# TIDA-00042_SCHEMAT_C.net
KiCad netlist of a schematic drawn in Altium Designer
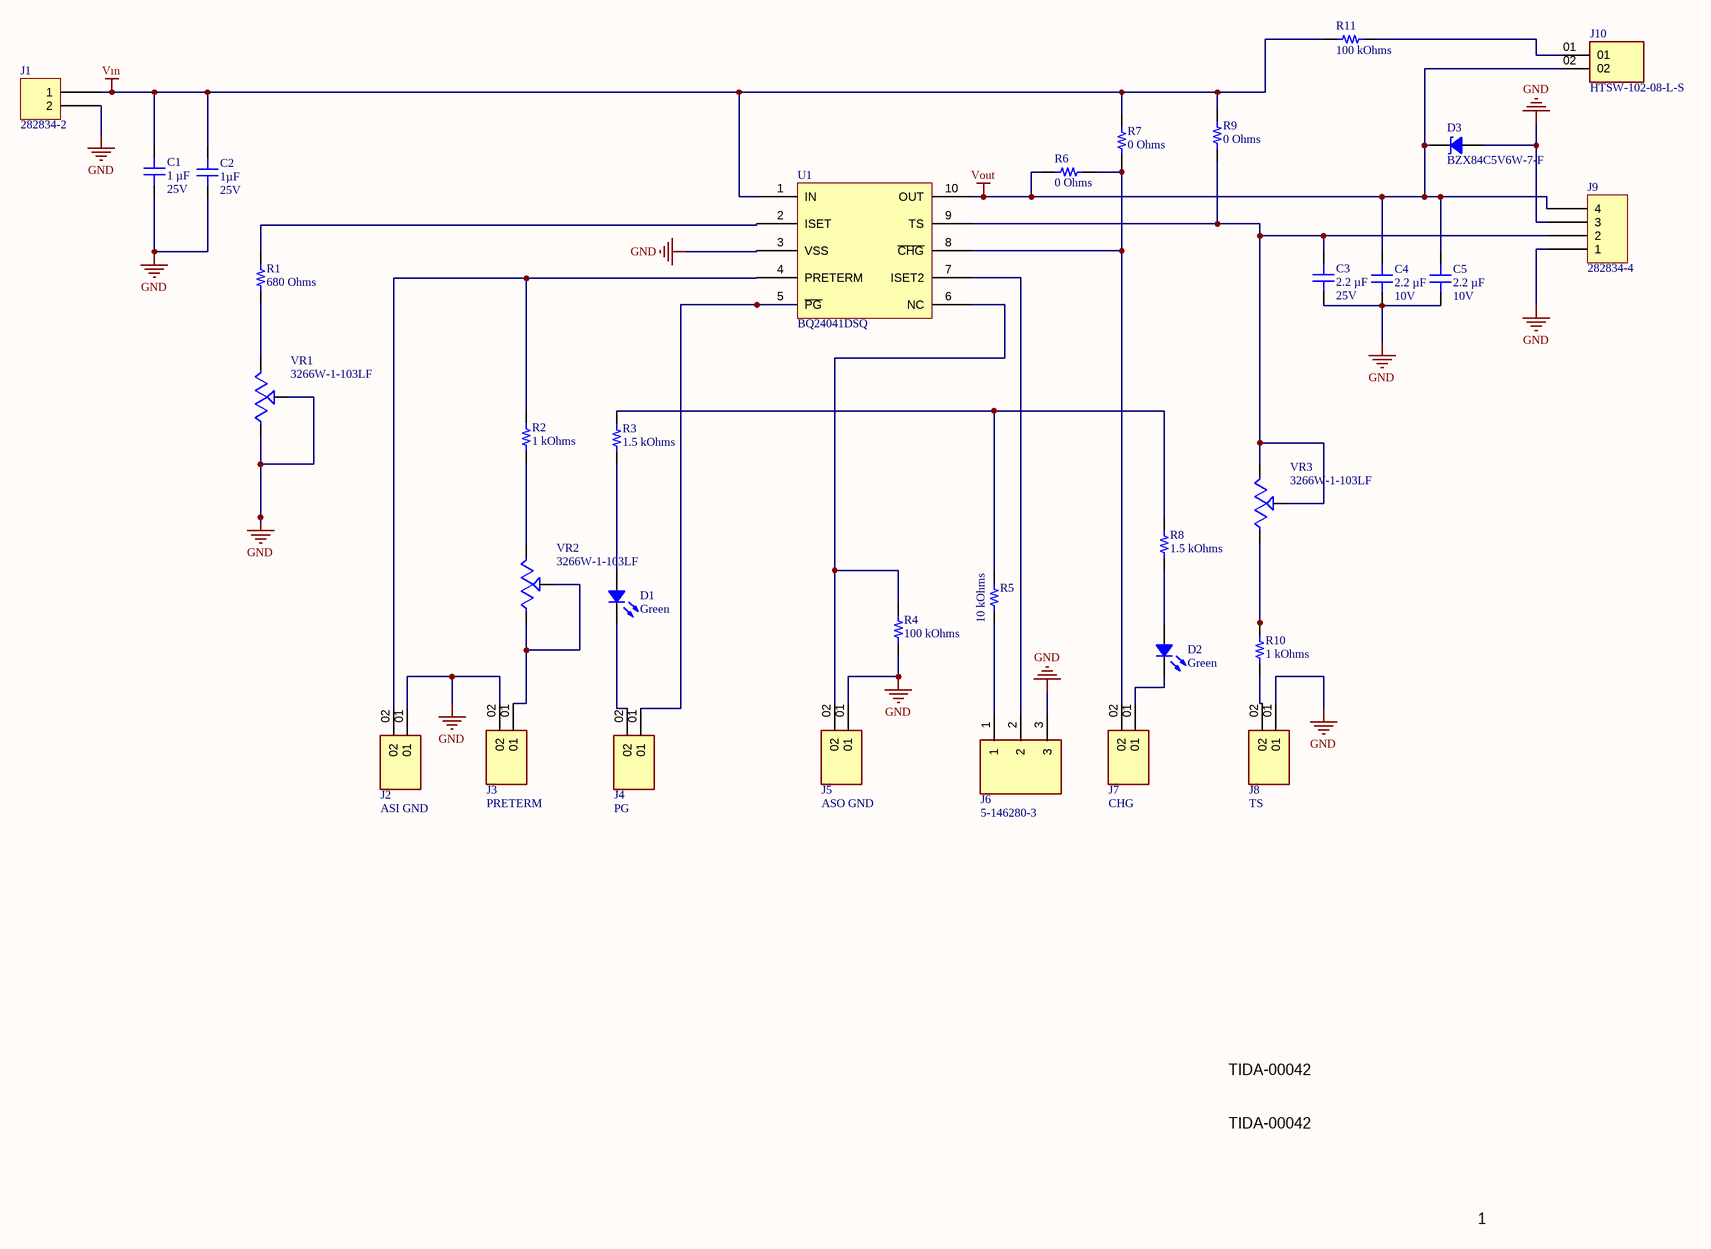
[diagram p0: TIDA-00042 SCHEMATİC.SchDoc]

(export (version "E")
  (design (tool "Eeschema 10.0.6"))
  (components
    (comp (ref "C1")
      (value "1 µF")
      (footprint "CAP 0603_1608")
      (description "CAP CER 1UF 25V X5R 0603")
      (fields
        (field (name "PART NUMBER") "CC0603KRX5R8BB105")
        (field (name "MANUFACTURER") "Yageo")
        (field (name "VOLTAGE - RATED") "25V")
      )
      (libsource (lib "Celestial Altium Library - altium_library") (part "Capacitor"))
    )
    (comp (ref "C2")
      (value "1µF")
      (footprint "CAP 0805_2012")
      (description "CAP CER 1UF 25V X5R 0805")
      (fields
        (field (name "PART NUMBER") "08053D105KAT2A")
        (field (name "MANUFACTURER") "AVX Corporation")
        (field (name "VOLTAGE - RATED") "25V")
      )
      (libsource (lib "Celestial Altium Library - altium_library") (part "Capacitor"))
    )
    (comp (ref "C3")
      (value "2.2 µF")
      (footprint "CAP 0603_1608")
      (description "CAP CER 2.2UF 25V X5R 0603")
      (fields
        (field (name "PART NUMBER") "CL10A225KA5LNNC")
        (field (name "MANUFACTURER") "Samsung Electro-Mechanics")
        (field (name "VOLTAGE - RATED") "25V")
      )
      (libsource (lib "Celestial Altium Library - altium_library") (part "Capacitor"))
    )
    (comp (ref "C4")
      (value "2.2 µF")
      (footprint "CAP 0603_1608")
      (description "CAP CER 2.2UF 10V X5R 0603")
      (fields
        (field (name "PART NUMBER") "CL10A225KP8NNNC")
        (field (name "MANUFACTURER") "Samsung Electro-Mechanics")
        (field (name "VOLTAGE - RATED") "10V")
      )
      (libsource (lib "Celestial Altium Library - altium_library") (part "Capacitor"))
    )
    (comp (ref "C5")
      (value "2.2 µF")
      (footprint "CAP 0805_2012")
      (description "CAP CER 2.2UF 10V X5R 0805")
      (fields
        (field (name "PART NUMBER") "CC0805KKX5R6BB225")
        (field (name "MANUFACTURER") "Yageo")
        (field (name "VOLTAGE - RATED") "10V")
      )
      (libsource (lib "Celestial Altium Library - altium_library") (part "Capacitor"))
    )
    (comp (ref "D1")
      (value "Green")
      (footprint "LED 0603_1608 GREEN")
      (description "LED GREEN CLEAR CHIP SMD")
      (fields (field (name "PART NUMBER") "LTST-C190GKT") (field (name "MANUFACTURER") "Lite-On Inc."))
      (libsource (lib "Celestial Altium Library - altium_library") (part "LED"))
    )
    (comp (ref "D2")
      (value "Green")
      (footprint "LED 0603_1608 GREEN")
      (description "LED GREEN CLEAR CHIP SMD")
      (fields (field (name "PART NUMBER") "LTST-C190GKT") (field (name "MANUFACTURER") "Lite-On Inc."))
      (libsource (lib "Celestial Altium Library - altium_library") (part "LED"))
    )
    (comp (ref "D3")
      (value "BZX84C5V6W-7-F")
      (footprint "DIODES SOT-323-3")
      (description "DIODE ZENER 5.6V 200MW SOT323")
      (fields (field (name "MANUFACTURER") "Diodes Incorporated") (field (name "TOLERANCE") "±7%"))
      (libsource (lib "Celestial Altium Library - altium_library") (part "Diode Zener"))
    )
    (comp (ref "J1")
      (value "282834-2")
      (footprint "TE 282834-2")
      (description "TERM BLK 2P SIDE ENT 2.54MM PCB")
      (fields (field (name "MANUFACTURER") "TE Connectivity AMP Connectors") (field (name "VOLTAGE") "150V"))
      (libsource (lib "Celestial Altium Library - altium_library") (part "2 Pin"))
    )
    (comp (ref "J2")
      (value "ASI GND")
      (footprint "SAMTEC_HTSW-102-08-L-S:SAMTEC_HTSW-102-08-L-S")
      (description "Conn Unshrouded Header HDR 2 POS 2.54mm Solder ST Top Entry Thru-Hole Bag")
      (fields (field (name "MP") "HTSW-102-08-L-S") (field (name "MF") "Samtec Inc."))
      (libsource (lib "HTSW-102-08-L-S") (part "HTSW-102-08-L-S"))
    )
    (comp (ref "J3")
      (value "PRETERM")
      (footprint "SAMTEC_HTSW-102-08-L-S:SAMTEC_HTSW-102-08-L-S")
      (description "Conn Unshrouded Header HDR 2 POS 2.54mm Solder ST Top Entry Thru-Hole Bag")
      (fields (field (name "MP") "HTSW-102-08-L-S") (field (name "MF") "Samtec Inc."))
      (libsource (lib "HTSW-102-08-L-S") (part "HTSW-102-08-L-S"))
    )
    (comp (ref "J4")
      (value "PG")
      (footprint "SAMTEC_HTSW-102-08-L-S:SAMTEC_HTSW-102-08-L-S")
      (description "Conn Unshrouded Header HDR 2 POS 2.54mm Solder ST Top Entry Thru-Hole Bag")
      (fields (field (name "MP") "HTSW-102-08-L-S") (field (name "MF") "Samtec Inc."))
      (libsource (lib "HTSW-102-08-L-S") (part "HTSW-102-08-L-S"))
    )
    (comp (ref "J5")
      (value "ASO GND")
      (footprint "SAMTEC_HTSW-102-08-L-S:SAMTEC_HTSW-102-08-L-S")
      (description "Conn Unshrouded Header HDR 2 POS 2.54mm Solder ST Top Entry Thru-Hole Bag")
      (fields (field (name "MP") "HTSW-102-08-L-S") (field (name "MF") "Samtec Inc."))
      (libsource (lib "HTSW-102-08-L-S") (part "HTSW-102-08-L-S"))
    )
    (comp (ref "J6")
      (value "5-146280-3")
      (footprint "SnapEDApcb:TE_5-146280-3")
      (description "Header; Conn; Interconnect System; PCB Plug; 3 Cont; Thru-Hole; Breakaway; Straight; 3A")
      (fields (field (name "MF") "TE Connectivity"))
      (libsource (lib "SnapEDAsch") (part "5-146280-3"))
    )
    (comp (ref "J7")
      (value "CHG")
      (footprint "SAMTEC_HTSW-102-08-L-S:SAMTEC_HTSW-102-08-L-S")
      (description "Conn Unshrouded Header HDR 2 POS 2.54mm Solder ST Top Entry Thru-Hole Bag")
      (fields (field (name "MP") "HTSW-102-08-L-S") (field (name "MF") "Samtec Inc."))
      (libsource (lib "HTSW-102-08-L-S") (part "HTSW-102-08-L-S"))
    )
    (comp (ref "J8")
      (value "TS")
      (footprint "SAMTEC_HTSW-102-08-L-S:SAMTEC_HTSW-102-08-L-S")
      (description "Conn Unshrouded Header HDR 2 POS 2.54mm Solder ST Top Entry Thru-Hole Bag")
      (fields (field (name "MP") "HTSW-102-08-L-S") (field (name "MF") "Samtec Inc."))
      (libsource (lib "HTSW-102-08-L-S") (part "HTSW-102-08-L-S"))
    )
    (comp (ref "J9")
      (value "282834-4")
      (footprint "TE 282834-4")
      (description "TERM BLK 4P SIDE ENT 2.54MM PCB")
      (fields (field (name "MANUFACTURER") "TE Connectivity AMP Connectors") (field (name "VOLTAGE") "150V"))
      (libsource (lib "Celestial Altium Library - altium_library") (part "4 Pin"))
    )
    (comp (ref "J10")
      (value "HTSW-102-08-L-S")
      (footprint "SAMTEC_HTSW-102-08-L-S:SAMTEC_HTSW-102-08-L-S")
      (description "Conn Unshrouded Header HDR 2 POS 2.54mm Solder ST Top Entry Thru-Hole Bag")
      (fields (field (name "MF") "Samtec Inc."))
      (libsource (lib "") (part "HTSW-102-08-L-S_1"))
    )
    (comp (ref "R1")
      (value "680 Ohms")
      (footprint "RES 0603_1608")
      (description "RES SMD 680 OHM 1% 1/10W 0603")
      (fields (field (name "PART NUMBER") "CRCW0603680RFKEA") (field (name "MANUFACTURER") "Vishay Dale"))
      (libsource (lib "Celestial Altium Library - altium_library") (part "Resistor"))
    )
    (comp (ref "R2")
      (value "1 kOhms")
      (footprint "RES 0603_1608")
      (description "RES SMD 1K OHM 1% 1/16W 0603")
      (fields
        (field (name "PART NUMBER") "CPF0603F1K0C1")
        (field (name "MANUFACTURER") "TE Connectivity Passive Product")
      )
      (libsource (lib "Celestial Altium Library - altium_library") (part "Resistor"))
    )
    (comp (ref "R3")
      (value "1.5 kOhms")
      (footprint "RES 0603_1608")
      (description "RES SMD 1.5K OHM 1% 1/10W 0603")
      (fields (field (name "PART NUMBER") "CRCW06031K50FKEA") (field (name "MANUFACTURER") "Vishay Dale"))
      (libsource (lib "Celestial Altium Library - altium_library") (part "Resistor"))
    )
    (comp (ref "R4")
      (value "100 kOhms")
      (footprint "RES 0603_1608")
      (description "RES 100K OHM 1% 1/10W 0603")
      (fields (field (name "PART NUMBER") "CRCW0603100KFKEBC") (field (name "MANUFACTURER") "Vishay Dale"))
      (libsource (lib "Celestial Altium Library - altium_library") (part "Resistor"))
    )
    (comp (ref "R5")
      (value "10 kOhms")
      (footprint "RES 0603_1608")
      (description "RES SMD 10K OHM 1% 1/16W 0603")
      (fields
        (field (name "PART NUMBER") "CPF0603F10KC1")
        (field (name "MANUFACTURER") "TE Connectivity Passive Product")
      )
      (libsource (lib "Celestial Altium Library - altium_library") (part "Resistor"))
    )
    (comp (ref "R6")
      (value "0 Ohms")
      (footprint "RES 0603_1608")
      (description "RES SMD 0 OHM JUMPER 1/10W 0603")
      (fields
        (field (name "PART NUMBER") "CRG0603ZR")
        (field (name "MANUFACTURER") "TE Connectivity Passive Product")
      )
      (libsource (lib "Celestial Altium Library - altium_library") (part "Resistor"))
    )
    (comp (ref "R7")
      (value "0 Ohms")
      (footprint "RES 0603_1608")
      (description "RES SMD 0 OHM JUMPER 1/10W 0603")
      (fields
        (field (name "PART NUMBER") "CRG0603ZR")
        (field (name "MANUFACTURER") "TE Connectivity Passive Product")
      )
      (libsource (lib "Celestial Altium Library - altium_library") (part "Resistor"))
    )
    (comp (ref "R8")
      (value "1.5 kOhms")
      (footprint "RES 0603_1608")
      (description "RES SMD 1.5K OHM 1% 1/10W 0603")
      (fields (field (name "PART NUMBER") "CRCW06031K50FKEA") (field (name "MANUFACTURER") "Vishay Dale"))
      (libsource (lib "Celestial Altium Library - altium_library") (part "Resistor"))
    )
    (comp (ref "R9")
      (value "0 Ohms")
      (footprint "RES 0603_1608")
      (description "RES SMD 0 OHM JUMPER 1/10W 0603")
      (fields
        (field (name "PART NUMBER") "CRG0603ZR")
        (field (name "MANUFACTURER") "TE Connectivity Passive Product")
      )
      (libsource (lib "Celestial Altium Library - altium_library") (part "Resistor"))
    )
    (comp (ref "R10")
      (value "1 kOhms")
      (footprint "RES 0603_1608")
      (description "RES SMD 1K OHM 1% 1/16W 0603")
      (fields
        (field (name "PART NUMBER") "CPF0603F1K0C1")
        (field (name "MANUFACTURER") "TE Connectivity Passive Product")
      )
      (libsource (lib "Celestial Altium Library - altium_library") (part "Resistor"))
    )
    (comp (ref "R11")
      (value "100 kOhms")
      (footprint "RES 0603_1608")
      (description "RES 100K OHM 1% 1/10W 0603")
      (fields (field (name "PART NUMBER") "CRCW0603100KFKEBC") (field (name "MANUFACTURER") "Vishay Dale"))
      (libsource (lib "Celestial Altium Library - altium_library") (part "Resistor"))
    )
    (comp (ref "U1")
      (value "BQ24041DSQ")
      (footprint "SON40P200X200X80-11N:SON40P200X200X80-11N")
      (libsource (lib "BQ24041DSQ") (part "BQ24041DSQ"))
    )
    (comp (ref "VR1")
      (value "3266W-1-103LF")
      (footprint "TRIM_3266W-1-103LF:TRIM_3266W-1-103LF")
      (description "10 kOhms 0.25W, 1/4W PC Pins Through Hole Trimmer Potentiometer Cermet 12 Turn Top Adjustment")
      (fields (field (name "MF") "Bourns"))
      (libsource (lib "3266W-1-103LF") (part "3266W-1-103LF"))
    )
    (comp (ref "VR2")
      (value "3266W-1-103LF")
      (footprint "TRIM_3266W-1-103LF:TRIM_3266W-1-103LF")
      (description "10 kOhms 0.25W, 1/4W PC Pins Through Hole Trimmer Potentiometer Cermet 12 Turn Top Adjustment")
      (fields (field (name "MF") "Bourns"))
      (libsource (lib "3266W-1-103LF") (part "3266W-1-103LF"))
    )
    (comp (ref "VR3")
      (value "3266W-1-103LF")
      (footprint "TRIM_3266W-1-103LF:TRIM_3266W-1-103LF")
      (description "10 kOhms 0.25W, 1/4W PC Pins Through Hole Trimmer Potentiometer Cermet 12 Turn Top Adjustment")
      (fields (field (name "MF") "Bourns"))
      (libsource (lib "3266W-1-103LF") (part "3266W-1-103LF"))
    )
  )
  (nets
    (net (code "1") (name "GND") (class "Default")
      (node (ref "C1") (pin "1") (pinfunction "1_1") (pintype "passive"))
      (node (ref "C2") (pin "1") (pinfunction "1_1") (pintype "passive"))
      (node (ref "C3") (pin "1") (pinfunction "1_1") (pintype "passive"))
      (node (ref "C4") (pin "1") (pinfunction "1_1") (pintype "passive"))
      (node (ref "C5") (pin "1") (pinfunction "1_1") (pintype "passive"))
      (node (ref "D3") (pin "1") (pinfunction "1_1") (pintype "passive"))
      (node (ref "J1") (pin "2") (pinfunction "2_2") (pintype "passive"))
      (node (ref "J2") (pin "01") (pinfunction "01_01") (pintype "passive"))
      (node (ref "J3") (pin "02") (pinfunction "02_02") (pintype "passive"))
      (node (ref "J5") (pin "01") (pinfunction "01_01") (pintype "passive"))
      (node (ref "J6") (pin "3") (pinfunction "3_3") (pintype "passive"))
      (node (ref "J8") (pin "01") (pinfunction "01_01") (pintype "passive"))
      (node (ref "J9") (pin "1") (pinfunction "1_1") (pintype "passive"))
      (node (ref "J9") (pin "3") (pinfunction "3_3") (pintype "passive"))
      (node (ref "R4") (pin "1") (pinfunction "1_1") (pintype "passive"))
      (node (ref "U1") (pin "3") (pinfunction "VSS_3") (pintype "passive"))
      (node (ref "VR1") (pin "1") (pinfunction "CCW_1") (pintype "passive"))
      (node (ref "VR1") (pin "2") (pinfunction "WIPER_2") (pintype "passive"))
    )
    (net (code "2") (name "Net-(D1-Pad1)") (class "Default")
      (node (ref "D1") (pin "1") (pinfunction "1_1") (pintype "passive"))
      (node (ref "R3") (pin "1") (pinfunction "1_1") (pintype "passive"))
    )
    (net (code "3") (name "Net-(D1-Pad2)") (class "Default")
      (node (ref "D1") (pin "2") (pinfunction "2_2") (pintype "passive"))
      (node (ref "J4") (pin "02") (pinfunction "02_02") (pintype "passive"))
    )
    (net (code "4") (name "Net-(D2-Pad1)") (class "Default")
      (node (ref "D2") (pin "1") (pinfunction "1_1") (pintype "passive"))
      (node (ref "R8") (pin "1") (pinfunction "1_1") (pintype "passive"))
    )
    (net (code "5") (name "Net-(D2-Pad2)") (class "Default")
      (node (ref "D2") (pin "2") (pinfunction "2_2") (pintype "passive"))
      (node (ref "J7") (pin "01") (pinfunction "01_01") (pintype "passive"))
    )
    (net (code "6") (name "Net-(J6-Pad1)") (class "Default")
      (node (ref "J6") (pin "1") (pinfunction "1_1") (pintype "passive"))
      (node (ref "R5") (pin "1") (pinfunction "1_1") (pintype "passive"))
    )
    (net (code "7") (name "Net-(J8-Pad02)") (class "Default")
      (node (ref "J8") (pin "02") (pinfunction "02_02") (pintype "passive"))
      (node (ref "R10") (pin "1") (pinfunction "1_1") (pintype "passive"))
    )
    (net (code "8") (name "Net-(J10-Pad01)") (class "Default")
      (node (ref "J10") (pin "01") (pinfunction "01_01") (pintype "passive"))
      (node (ref "R11") (pin "2") (pinfunction "2_2") (pintype "passive"))
    )
    (net (code "9") (name "Net-(R3-Pad2)") (class "Default")
      (node (ref "R3") (pin "2") (pinfunction "2_2") (pintype "passive"))
      (node (ref "R5") (pin "2") (pinfunction "2_2") (pintype "passive"))
      (node (ref "R8") (pin "2") (pinfunction "2_2") (pintype "passive"))
    )
    (net (code "10") (name "Net-(U1-ISET)") (class "Default")
      (node (ref "R1") (pin "2") (pinfunction "2_2") (pintype "passive"))
      (node (ref "U1") (pin "2") (pinfunction "ISET_2") (pintype "passive"))
    )
    (net (code "11") (name "Net-(U1-ISET2)") (class "Default")
      (node (ref "J6") (pin "2") (pinfunction "2_2") (pintype "passive"))
      (node (ref "U1") (pin "7") (pinfunction "ISET2_7") (pintype "passive"))
    )
    (net (code "12") (name "Net-(U1-NC)") (class "Default")
      (node (ref "J5") (pin "02") (pinfunction "02_02") (pintype "passive"))
      (node (ref "R4") (pin "2") (pinfunction "2_2") (pintype "passive"))
      (node (ref "U1") (pin "6") (pinfunction "NC_6") (pintype "passive"))
    )
    (net (code "13") (name "Net-(U1-PRETERM)") (class "Default")
      (node (ref "J2") (pin "02") (pinfunction "02_02") (pintype "passive"))
      (node (ref "R2") (pin "2") (pinfunction "2_2") (pintype "passive"))
      (node (ref "U1") (pin "4") (pinfunction "PRETERM_4") (pintype "passive"))
    )
    (net (code "14") (name "Net-(U1-TS)") (class "Default")
      (node (ref "C3") (pin "2") (pinfunction "2_2") (pintype "passive"))
      (node (ref "J9") (pin "2") (pinfunction "2_2") (pintype "passive"))
      (node (ref "R9") (pin "1") (pinfunction "1_1") (pintype "passive"))
      (node (ref "U1") (pin "9") (pinfunction "TS_9") (pintype "passive"))
      (node (ref "VR3") (pin "2") (pinfunction "WIPER_2") (pintype "passive"))
      (node (ref "VR3") (pin "3") (pinfunction "CW_3") (pintype "passive"))
    )
    (net (code "15") (name "Net-(U1-~{CHG})") (class "Default")
      (node (ref "J7") (pin "02") (pinfunction "02_02") (pintype "passive"))
      (node (ref "R6") (pin "1") (pinfunction "1_1") (pintype "passive"))
      (node (ref "R7") (pin "1") (pinfunction "1_1") (pintype "passive"))
      (node (ref "U1") (pin "8") (pinfunction "~{CHG}_8") (pintype "passive"))
    )
    (net (code "16") (name "Net-(U1-~{PG})") (class "Default")
      (node (ref "J4") (pin "01") (pinfunction "01_01") (pintype "passive"))
      (node (ref "U1") (pin "5") (pinfunction "~{PG}_5") (pintype "passive"))
    )
    (net (code "17") (name "Net-(VR1-CW)") (class "Default")
      (node (ref "R1") (pin "1") (pinfunction "1_1") (pintype "passive"))
      (node (ref "VR1") (pin "3") (pinfunction "CW_3") (pintype "passive"))
    )
    (net (code "18") (name "Net-(VR2-CCW)") (class "Default")
      (node (ref "J3") (pin "01") (pinfunction "01_01") (pintype "passive"))
      (node (ref "VR2") (pin "1") (pinfunction "CCW_1") (pintype "passive"))
      (node (ref "VR2") (pin "2") (pinfunction "WIPER_2") (pintype "passive"))
    )
    (net (code "19") (name "Net-(VR2-CW)") (class "Default")
      (node (ref "R2") (pin "1") (pinfunction "1_1") (pintype "passive"))
      (node (ref "VR2") (pin "3") (pinfunction "CW_3") (pintype "passive"))
    )
    (net (code "20") (name "Net-(VR3-CCW)") (class "Default")
      (node (ref "R10") (pin "2") (pinfunction "2_2") (pintype "passive"))
      (node (ref "VR3") (pin "1") (pinfunction "CCW_1") (pintype "passive"))
    )
    (net (code "21") (name "Vout") (class "Default")
      (node (ref "C4") (pin "2") (pinfunction "2_2") (pintype "passive"))
      (node (ref "C5") (pin "2") (pinfunction "2_2") (pintype "passive"))
      (node (ref "D3") (pin "2") (pinfunction "2_2") (pintype "passive"))
      (node (ref "J10") (pin "02") (pinfunction "02_02") (pintype "passive"))
      (node (ref "J9") (pin "4") (pinfunction "4_4") (pintype "passive"))
      (node (ref "R6") (pin "2") (pinfunction "2_2") (pintype "passive"))
      (node (ref "U1") (pin "10") (pinfunction "OUT_10") (pintype "passive"))
    )
    (net (code "22") (name "Vın") (class "Default")
      (node (ref "C1") (pin "2") (pinfunction "2_2") (pintype "passive"))
      (node (ref "C2") (pin "2") (pinfunction "2_2") (pintype "passive"))
      (node (ref "J1") (pin "1") (pinfunction "1_1") (pintype "passive"))
      (node (ref "R11") (pin "1") (pinfunction "1_1") (pintype "passive"))
      (node (ref "R7") (pin "2") (pinfunction "2_2") (pintype "passive"))
      (node (ref "R9") (pin "2") (pinfunction "2_2") (pintype "passive"))
      (node (ref "U1") (pin "1") (pinfunction "IN_1") (pintype "passive"))
    )
  )
)
